# UpTo11_FrontPanel.net
KiCad netlist of a schematic drawn in EAGLE
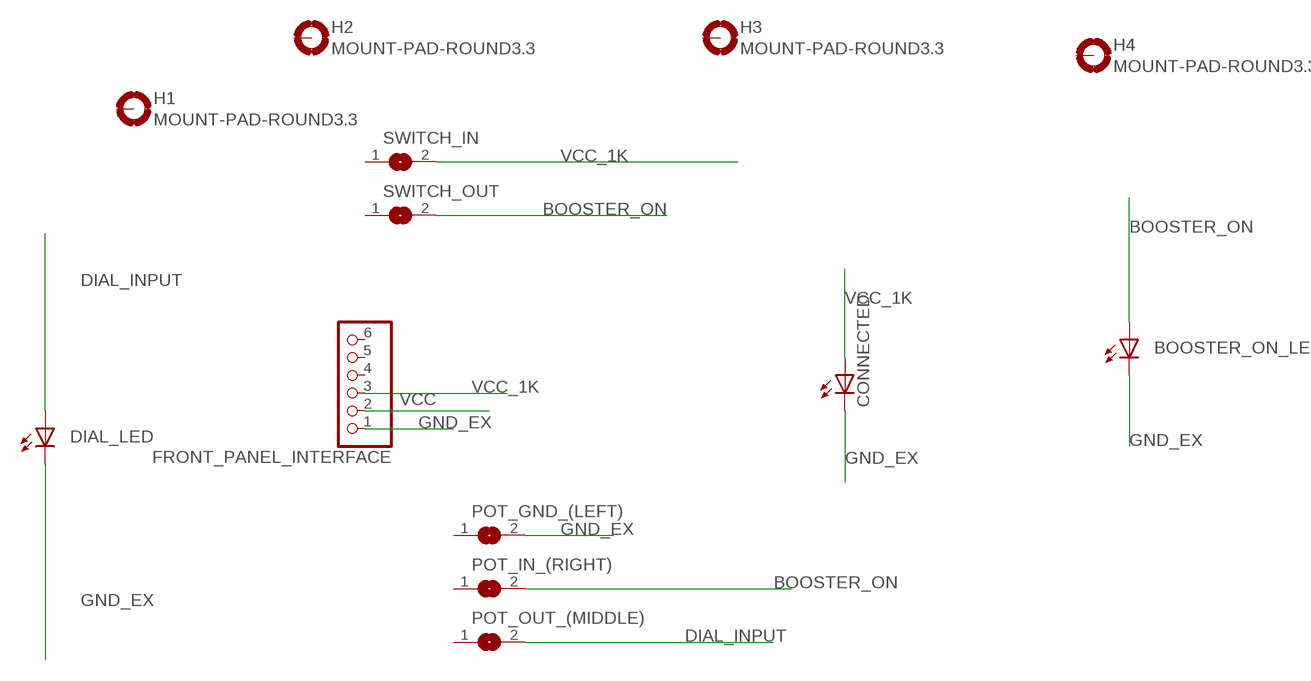
[diagram p0: schematic, sheet 1]

(export (version "E")
  (design (tool "Eeschema 10.0.6"))
  (components
    (comp (ref "BOOSTER_ON_LED")
      (value "LED5MM")
      (footprint "eagle-import:LED5MM")
      (libsource (lib "eagle-import") (part "LED5MM"))
    )
    (comp (ref "CONNECTED")
      (value "LEDSMT1206")
      (footprint "eagle-import:1206")
      (libsource (lib "eagle-import") (part "LEDSMT1206"))
    )
    (comp (ref "DIAL_LED")
      (value "LED5MM")
      (footprint "eagle-import:LED5MM")
      (libsource (lib "eagle-import") (part "LED5MM"))
    )
    (comp (ref "FRONT_PANEL_INTERFACE")
      (value "PINHD-1X6")
      (footprint "eagle-import:1X06")
      (libsource (lib "eagle-import") (part "PINHD-1X6"))
    )
    (comp (ref "H1")
      (value "MOUNT-PAD-ROUND3.3")
      (footprint "eagle-import:3,3-PAD")
      (libsource (lib "eagle-import") (part "MOUNT-PAD-ROUND3.3"))
    )
    (comp (ref "H2")
      (value "MOUNT-PAD-ROUND3.3")
      (footprint "eagle-import:3,3-PAD")
      (libsource (lib "eagle-import") (part "MOUNT-PAD-ROUND3.3"))
    )
    (comp (ref "H3")
      (value "MOUNT-PAD-ROUND3.3")
      (footprint "eagle-import:3,3-PAD")
      (libsource (lib "eagle-import") (part "MOUNT-PAD-ROUND3.3"))
    )
    (comp (ref "H4")
      (value "MOUNT-PAD-ROUND3.3")
      (footprint "eagle-import:3,3-PAD")
      (libsource (lib "eagle-import") (part "MOUNT-PAD-ROUND3.3"))
    )
    (comp (ref "POT_GND_(LEFT)")
      (value "SOLDERJUMPERREFLOW")
      (footprint "eagle-import:SOLDERJUMPER_REFLOW")
      (libsource (lib "eagle-import") (part "SOLDERJUMPERREFLOW"))
    )
    (comp (ref "POT_IN_(RIGHT)")
      (value "SOLDERJUMPERREFLOW")
      (footprint "eagle-import:SOLDERJUMPER_REFLOW")
      (libsource (lib "eagle-import") (part "SOLDERJUMPERREFLOW"))
    )
    (comp (ref "POT_OUT_(MIDDLE)")
      (value "SOLDERJUMPERREFLOW")
      (footprint "eagle-import:SOLDERJUMPER_REFLOW")
      (libsource (lib "eagle-import") (part "SOLDERJUMPERREFLOW"))
    )
    (comp (ref "SWITCH_IN")
      (value "SOLDERJUMPERREFLOW")
      (footprint "eagle-import:SOLDERJUMPER_REFLOW")
      (libsource (lib "eagle-import") (part "SOLDERJUMPERREFLOW"))
    )
    (comp (ref "SWITCH_OUT")
      (value "SOLDERJUMPERREFLOW")
      (footprint "eagle-import:SOLDERJUMPER_REFLOW")
      (libsource (lib "eagle-import") (part "SOLDERJUMPERREFLOW"))
    )
  )
  (nets
    (net (code "1") (name "/BOOSTER_ON") (class "Default")
      (node (ref "BOOSTER_ON_LED") (pin "A") (pinfunction "A_A") (pintype "passive"))
      (node (ref "POT_IN_(RIGHT)") (pin "2") (pinfunction "2_2") (pintype "passive"))
      (node (ref "SWITCH_OUT") (pin "2") (pinfunction "2_2") (pintype "passive"))
    )
    (net (code "2") (name "/DIAL_INPUT") (class "Default")
      (node (ref "DIAL_LED") (pin "A") (pinfunction "A_A") (pintype "passive"))
      (node (ref "POT_OUT_(MIDDLE)") (pin "2") (pinfunction "2_2") (pintype "passive"))
    )
    (net (code "3") (name "/GND_EX") (class "Default")
      (node (ref "BOOSTER_ON_LED") (pin "K") (pinfunction "C_K") (pintype "passive"))
      (node (ref "CONNECTED") (pin "C") (pinfunction "C_C") (pintype "passive"))
      (node (ref "DIAL_LED") (pin "K") (pinfunction "C_K") (pintype "passive"))
      (node (ref "FRONT_PANEL_INTERFACE") (pin "1") (pinfunction "1_1") (pintype "passive"))
      (node (ref "POT_GND_(LEFT)") (pin "2") (pinfunction "2_2") (pintype "passive"))
    )
    (net (code "4") (name "/VCC") (class "Default")
      (node (ref "FRONT_PANEL_INTERFACE") (pin "2") (pinfunction "2_2") (pintype "passive"))
    )
    (net (code "5") (name "/VCC_1K") (class "Default")
      (node (ref "CONNECTED") (pin "A") (pinfunction "A_A") (pintype "passive"))
      (node (ref "FRONT_PANEL_INTERFACE") (pin "3") (pinfunction "3_3") (pintype "passive"))
      (node (ref "SWITCH_IN") (pin "2") (pinfunction "2_2") (pintype "passive"))
    )
    (net (code "6") (name "unconnected-(FRONT_PANEL_INTERFACE-Pad4)") (class "Default")
      (node (ref "FRONT_PANEL_INTERFACE") (pin "4") (pinfunction "4_4") (pintype "passive"))
    )
    (net (code "7") (name "unconnected-(FRONT_PANEL_INTERFACE-Pad5)") (class "Default")
      (node (ref "FRONT_PANEL_INTERFACE") (pin "5") (pinfunction "5_5") (pintype "passive"))
    )
    (net (code "8") (name "unconnected-(FRONT_PANEL_INTERFACE-Pad6)") (class "Default")
      (node (ref "FRONT_PANEL_INTERFACE") (pin "6") (pinfunction "6_6") (pintype "passive"))
    )
    (net (code "9") (name "unconnected-(H1-MOUNT-PadB3,3)") (class "Default")
      (node (ref "H1") (pin "B3,3") (pinfunction "MOUNT_B3,3") (pintype "passive"))
    )
    (net (code "10") (name "unconnected-(H2-MOUNT-PadB3,3)") (class "Default")
      (node (ref "H2") (pin "B3,3") (pinfunction "MOUNT_B3,3") (pintype "passive"))
    )
    (net (code "11") (name "unconnected-(H3-MOUNT-PadB3,3)") (class "Default")
      (node (ref "H3") (pin "B3,3") (pinfunction "MOUNT_B3,3") (pintype "passive"))
    )
    (net (code "12") (name "unconnected-(H4-MOUNT-PadB3,3)") (class "Default")
      (node (ref "H4") (pin "B3,3") (pinfunction "MOUNT_B3,3") (pintype "passive"))
    )
    (net (code "13") (name "unconnected-(POT_GND_(LEFT)-Pad1)") (class "Default")
      (node (ref "POT_GND_(LEFT)") (pin "1") (pinfunction "1_1") (pintype "passive"))
    )
    (net (code "14") (name "unconnected-(POT_IN_(RIGHT)-Pad1)") (class "Default")
      (node (ref "POT_IN_(RIGHT)") (pin "1") (pinfunction "1_1") (pintype "passive"))
    )
    (net (code "15") (name "unconnected-(POT_OUT_(MIDDLE)-Pad1)") (class "Default")
      (node (ref "POT_OUT_(MIDDLE)") (pin "1") (pinfunction "1_1") (pintype "passive"))
    )
    (net (code "16") (name "unconnected-(SWITCH_IN-Pad1)") (class "Default")
      (node (ref "SWITCH_IN") (pin "1") (pinfunction "1_1") (pintype "passive"))
    )
    (net (code "17") (name "unconnected-(SWITCH_OUT-Pad1)") (class "Default")
      (node (ref "SWITCH_OUT") (pin "1") (pinfunction "1_1") (pintype "passive"))
    )
  )
)
